# PAGE2_ATMEL.net
KiCad netlist of a schematic drawn in Altium Designer
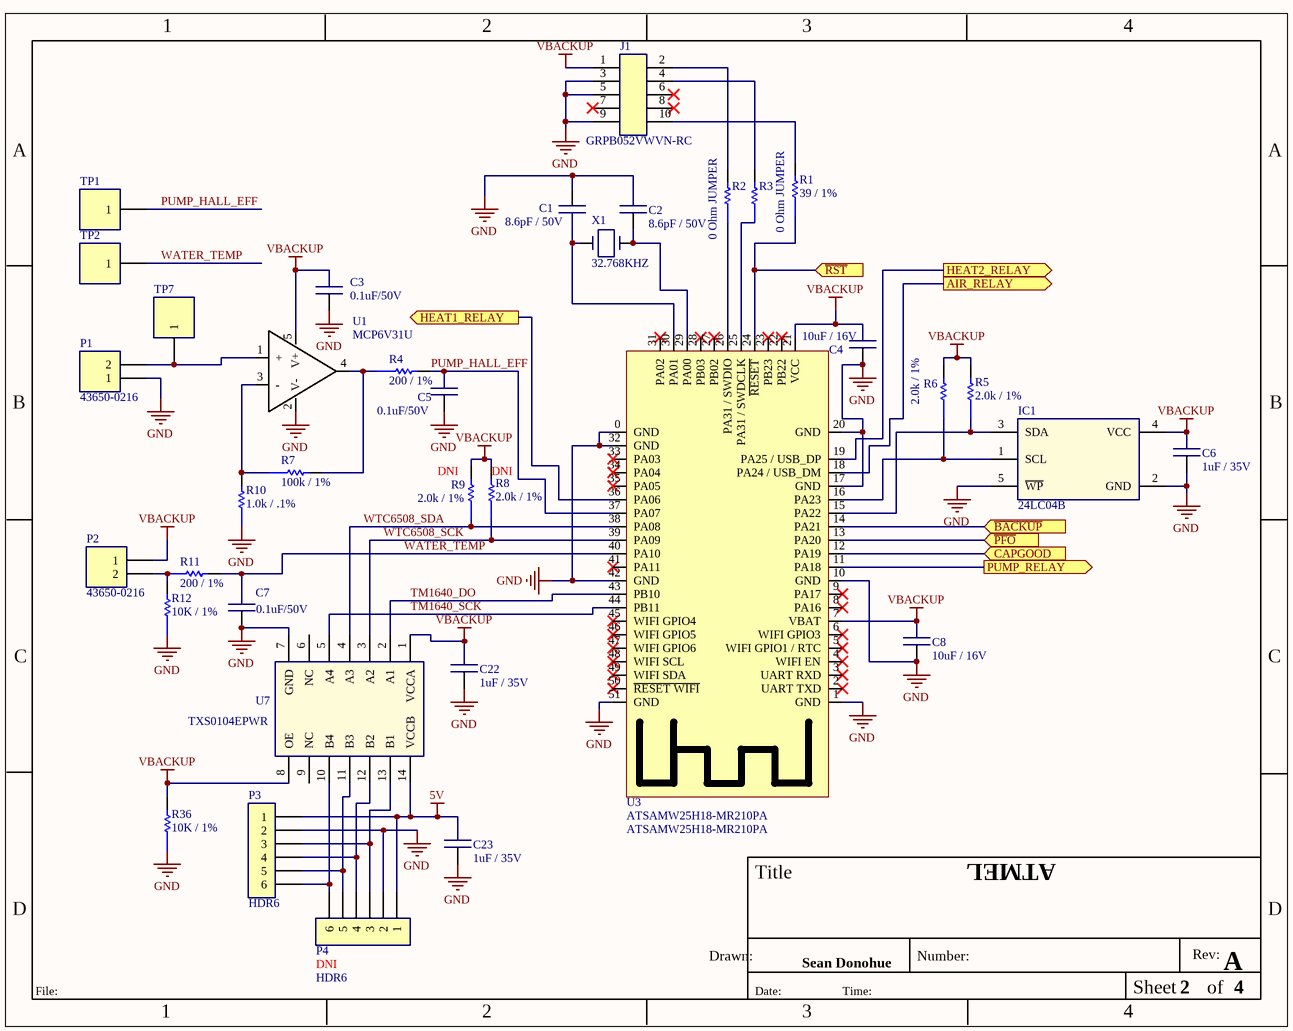
[diagram p0: PAGE2_ATMEL.SchDoc]

(export (version "E")
  (design (tool "Eeschema 10.0.6"))
  (components
    (comp (ref "C1")
      (value "8.6pF / 50V")
      (footprint "0603")
      (description "CAP CER 8.2PF 50V NP0 0603")
      (fields (field (name "MFG") "KEMET") (field (name "Comment") "cap"))
      (libsource (lib "eetrex comp db") (part "cap"))
    )
    (comp (ref "C2")
      (value "8.6pF / 50V")
      (footprint "0603")
      (description "CAP CER 8.2PF 50V NP0 0603")
      (fields (field (name "MFG") "KEMET") (field (name "Comment") "cap"))
      (libsource (lib "eetrex comp db") (part "cap"))
    )
    (comp (ref "C3")
      (value "0.1uF/50V")
      (footprint "0603")
      (description "CAP CER 0.1UF 50V 10% X7R 0603")
      (fields (field (name "MFG") "Murata") (field (name "Comment") "cap"))
      (libsource (lib "eetrex comp db") (part "cap"))
    )
    (comp (ref "C4")
      (value "10uF / 16V")
      (footprint "0603")
      (description "CAP CER 10UF 16V X5R 0603")
      (fields (field (name "MFG") "Taiyo Uden") (field (name "Comment") "cap"))
      (libsource (lib "eetrex comp db") (part "cap"))
    )
    (comp (ref "C5")
      (value "0.1uF/50V")
      (footprint "0603")
      (description "CAP CER 0.1UF 50V 10% X7R 0603")
      (fields (field (name "MFG") "Murata") (field (name "Comment") "cap"))
      (libsource (lib "eetrex comp db") (part "cap"))
    )
    (comp (ref "C6")
      (value "1uF / 35V")
      (footprint "0603")
      (description "CAP CER 1UF 35V X7R 0603")
      (fields (field (name "MFG") "Murata") (field (name "Comment") "cap"))
      (libsource (lib "eetrex comp db") (part "cap"))
    )
    (comp (ref "C7")
      (value "0.1uF/50V")
      (footprint "0603")
      (description "CAP CER 0.1UF 50V 10% X7R 0603")
      (fields (field (name "MFG") "Murata") (field (name "Comment") "cap"))
      (libsource (lib "eetrex comp db") (part "cap"))
    )
    (comp (ref "C8")
      (value "10uF / 16V")
      (footprint "0603")
      (description "CAP CER 10UF 16V X5R 0603")
      (fields (field (name "MFG") "Taiyo Uden") (field (name "Comment") "cap"))
      (libsource (lib "eetrex comp db") (part "cap"))
    )
    (comp (ref "C22")
      (value "1uF / 35V")
      (footprint "0603")
      (description "CAP CER 1UF 35V X7R 0603")
      (fields (field (name "MFG") "Murata") (field (name "Comment") "cap"))
      (libsource (lib "eetrex comp db") (part "cap"))
    )
    (comp (ref "C23")
      (value "1uF / 35V")
      (footprint "0603")
      (description "CAP CER 1UF 35V X7R 0603")
      (fields (field (name "MFG") "Murata") (field (name "Comment") "cap"))
      (libsource (lib "eetrex comp db") (part "cap"))
    )
    (comp (ref "IC1")
      (value "24LC04B")
      (footprint "SOT-23-5")
      (description "IC SERIAL EEPROM 4K 2.5V SOT23-5")
      (fields (field (name "MFG") "Microchip"))
      (libsource (lib "eetrex comp db") (part "24LC04B"))
    )
    (comp (ref "J1")
      (value "GRPB052VWVN-RC")
      (footprint "conn_10p_050mil")
      (description "CONN HEADER 10POS 1.27MM GOLD T/H")
      (fields (field (name "MFG") "Sullins") (field (name "Comment") "Header 10D"))
      (libsource (lib "eetrex comp db") (part "Header 10D"))
    )
    (comp (ref "P1")
      (value "43650-0216")
      (footprint "conn_molex_2p_43650-0215")
      (description "CONN HEADER 2POS 3MM VERT GOLD")
      (fields (field (name "MFG") "Molex") (field (name "Comment") "Header 2"))
      (libsource (lib "eetrex comp db") (part "Header 2"))
    )
    (comp (ref "P2")
      (value "43650-0216")
      (footprint "conn_molex_2p_43650-0215")
      (description "CONN HEADER 2POS 3MM VERT GOLD")
      (fields (field (name "MFG") "Molex") (field (name "Comment") "Header 2"))
      (libsource (lib "") (part "Header 2_1"))
    )
    (comp (ref "P3")
      (value "HDR6")
      (footprint "HDR1X6")
      (description "CONN HEADER 6POS .330 tall, TIN")
      (fields (field (name "MFG") "Samtec") (field (name "Comment") "Header 6"))
      (libsource (lib "eetrex comp db") (part "Header 6"))
    )
    (comp (ref "P4")
      (value "HDR6")
      (footprint "HDR1X6")
      (description "CONN HEADER 6POS .330 tall, TIN")
      (fields (field (name "MFG") "Samtec") (field (name "LOAD") "DNI") (field (name "Comment") "Header 6"))
      (libsource (lib "eetrex comp db") (part "Header 6"))
    )
    (comp (ref "R1")
      (value "39 / 1%")
      (footprint "0603")
      (description "RES 39 OHM 1% 1/10W 0603 SMD")
      (fields (field (name "MFG") "Panasonic") (field (name "Comment") "Res"))
      (libsource (lib "eetrex comp db") (part "Res"))
    )
    (comp (ref "R2")
      (value " 0 Ohm JUMPER")
      (footprint "0603")
      (description "RES 0.0 OHM 1/10W 0603 SMD")
      (fields (field (name "MFG") "Stackpole") (field (name "Comment") "Res"))
      (libsource (lib "eetrex comp db") (part "Res"))
    )
    (comp (ref "R3")
      (value " 0 Ohm JUMPER")
      (footprint "0603")
      (description "RES 0.0 OHM 1/10W 0603 SMD")
      (fields (field (name "MFG") "Stackpole") (field (name "Comment") "Res"))
      (libsource (lib "eetrex comp db") (part "Res"))
    )
    (comp (ref "R4")
      (value "200 / 1%")
      (footprint "0603")
      (description "RES 200 OHM 1% 1/10W 0603 SMD")
      (fields (field (name "MFG") "Panasonic") (field (name "Comment") "Res"))
      (libsource (lib "eetrex comp db") (part "Res"))
    )
    (comp (ref "R5")
      (value "2.0k / 1%")
      (footprint "0603")
      (description "RES 2.00K OHM 1/10W 1% 0603 SMD")
      (fields (field (name "MFG") "Vishay") (field (name "Comment") "Res"))
      (libsource (lib "eetrex comp db") (part "Res"))
    )
    (comp (ref "R6")
      (value "2.0k / 1%")
      (footprint "0603")
      (description "RES 2.00K OHM 1/10W 1% 0603 SMD")
      (fields (field (name "MFG") "Vishay") (field (name "Comment") "Res"))
      (libsource (lib "eetrex comp db") (part "Res"))
    )
    (comp (ref "R7")
      (value "100k / 1%")
      (footprint "0603")
      (description "RES 100K OHM 1/10W 1% 0603 SMD")
      (fields (field (name "MFG") "Panasonic") (field (name "Comment") "Res"))
      (libsource (lib "eetrex comp db") (part "Res"))
    )
    (comp (ref "R8")
      (value "2.0k / 1%")
      (footprint "0603")
      (description "RES 2.00K OHM 1/10W 1% 0603 SMD")
      (fields (field (name "MFG") "Vishay") (field (name "LOAD") "DNI") (field (name "Comment") "Res"))
      (libsource (lib "eetrex comp db") (part "Res"))
    )
    (comp (ref "R9")
      (value "2.0k / 1%")
      (footprint "0603")
      (description "RES 2.00K OHM 1/10W 1% 0603 SMD")
      (fields (field (name "MFG") "Vishay") (field (name "LOAD") "DNI") (field (name "Comment") "Res"))
      (libsource (lib "eetrex comp db") (part "Res"))
    )
    (comp (ref "R10")
      (value "1.0k / .1%")
      (footprint "0603")
      (description "RES 1.0K OHM 1/10W .1% 0603 SMD")
      (fields (field (name "MFG") "Panasonic") (field (name "Comment") "Res"))
      (libsource (lib "eetrex comp db") (part "Res"))
    )
    (comp (ref "R11")
      (value "200 / 1%")
      (footprint "0603")
      (description "RES 200 OHM 1% 1/10W 0603 SMD")
      (fields (field (name "MFG") "Panasonic") (field (name "Comment") "Res"))
      (libsource (lib "eetrex comp db") (part "Res"))
    )
    (comp (ref "R12")
      (value "10K / 1%")
      (footprint "0603")
      (description "RES 10K OHM 1% 1/8W 0603 SMD")
      (fields (field (name "MFG") "Vishay") (field (name "Comment") "Res"))
      (libsource (lib "eetrex comp db") (part "Res"))
    )
    (comp (ref "R36")
      (value "10K / 1%")
      (footprint "0603")
      (description "RES 10K OHM 1% 1/8W 0603 SMD")
      (fields (field (name "MFG") "Vishay") (field (name "Comment") "Res"))
      (libsource (lib "eetrex comp db") (part "Res"))
    )
    (comp (ref "TP1")
      (value "Header 1")
      (footprint "HDR1")
      (description "CONN HEADER 1POS .330 tall, TIN")
      (fields (field (name "MFG") "Samtec"))
      (libsource (lib "eetrex comp db") (part "Header 1"))
    )
    (comp (ref "TP2")
      (value "Header 1")
      (footprint "HDR1")
      (description "CONN HEADER 1POS .330 tall, TIN")
      (fields (field (name "MFG") "Samtec"))
      (libsource (lib "eetrex comp db") (part "Header 1"))
    )
    (comp (ref "TP7")
      (value "Header 1")
      (footprint "HDR1")
      (description "CONN HEADER 1POS .330 tall, TIN")
      (fields (field (name "MFG") "Samtec"))
      (libsource (lib "") (part "Header 1_1"))
    )
    (comp (ref "U1")
      (value "MCP6V31U")
      (footprint "SOT-23-5")
      (description "IC OPAMP ZRO-DRFT 300KHZ SC70-5")
      (fields (field (name "MFG") "MicroChip"))
      (libsource (lib "eetrex comp db") (part "MCP6V31U"))
    )
    (comp (ref "U3")
      (value "ATSAMW25H18-MR210PA")
      (footprint "ATSAMW25H18-MR210PA")
      (description "RF TXRX MODULE WIFI TRACE ANT")
      (fields (field (name "ALTIUM_VALUE") "ATSAMW25H18-MR210PA") (field (name "MFG") "Atmel"))
      (libsource (lib "eetrex comp db") (part "ATSAMW25H18-MR210PA"))
    )
    (comp (ref "U7")
      (value "TXS0104EPWR")
      (footprint "TSSOP-14")
      (description "IC 4BIT NON-INV TRANSLTR 14TSSOP")
      (fields (field (name "MFG") "Texas Instruments"))
      (libsource (lib "eetrex comp db") (part "TXS0104EPWR"))
    )
    (comp (ref "X1")
      (value "32.768KHZ")
      (footprint "FC-13F")
      (description "CRYSTAL 32.768KHZ 7PF SMD")
      (fields (field (name "MFG") "AVX") (field (name "Comment") "crystal"))
      (libsource (lib "eetrex comp db") (part "crystal"))
    )
  )
  (nets
    (net (code "1") (name "/AIR_RELAY") (class "Default")
      (node (ref "U3") (pin "18") (pinfunction "PA24_/_USB_DM_18") (pintype "passive"))
    )
    (net (code "2") (name "/CAPGOOD") (class "Default")
      (node (ref "U3") (pin "12") (pinfunction "PA19_12") (pintype "passive"))
    )
    (net (code "3") (name "/HEAT1_RELAY") (class "Default")
      (node (ref "U3") (pin "36") (pinfunction "PA06_36") (pintype "passive"))
    )
    (net (code "4") (name "/HEAT2_RELAY") (class "Default")
      (node (ref "U3") (pin "19") (pinfunction "PA25_/_USB_DP_19") (pintype "passive"))
    )
    (net (code "5") (name "/PUMP_HALL_EFF") (class "Default")
      (node (ref "C5") (pin "1") (pinfunction "1_1") (pintype "passive"))
      (node (ref "R4") (pin "2") (pinfunction "2_2") (pintype "passive"))
      (node (ref "TP1") (pin "1") (pinfunction "1_1") (pintype "passive"))
      (node (ref "U3") (pin "37") (pinfunction "PA07_37") (pintype "passive"))
    )
    (net (code "6") (name "/PUMP_RELAY") (class "Default")
      (node (ref "U3") (pin "11") (pinfunction "PA18_11") (pintype "passive"))
    )
    (net (code "7") (name "/TM1640_DO") (class "Default")
      (node (ref "U3") (pin "43") (pinfunction "PB10_43") (pintype "passive"))
      (node (ref "U7") (pin "2") (pinfunction "A1_2") (pintype "passive"))
    )
    (net (code "8") (name "/TM1640_SCK") (class "Default")
      (node (ref "U3") (pin "44") (pinfunction "PB11_44") (pintype "passive"))
      (node (ref "U7") (pin "5") (pinfunction "A4_5") (pintype "passive"))
    )
    (net (code "9") (name "/WATER_TEMP") (class "Default")
      (node (ref "C7") (pin "1") (pinfunction "1_1") (pintype "passive"))
      (node (ref "R11") (pin "2") (pinfunction "2_2") (pintype "passive"))
      (node (ref "TP2") (pin "1") (pinfunction "1_1") (pintype "passive"))
      (node (ref "U3") (pin "40") (pinfunction "PA10_40") (pintype "passive"))
    )
    (net (code "10") (name "/WTC6508_SCK") (class "Default")
      (node (ref "R8") (pin "1") (pinfunction "1_1") (pintype "passive"))
      (node (ref "U3") (pin "39") (pinfunction "PA09_39") (pintype "passive"))
      (node (ref "U7") (pin "3") (pinfunction "A2_3") (pintype "passive"))
    )
    (net (code "11") (name "/WTC6508_SDA") (class "Default")
      (node (ref "R9") (pin "1") (pinfunction "1_1") (pintype "passive"))
      (node (ref "U3") (pin "38") (pinfunction "PA08_38") (pintype "passive"))
      (node (ref "U7") (pin "4") (pinfunction "A3_4") (pintype "passive"))
    )
    (net (code "12") (name "/~{BACKUP}") (class "Default")
      (node (ref "U3") (pin "14") (pinfunction "PA21_14") (pintype "passive"))
    )
    (net (code "13") (name "/~{PFO}") (class "Default")
      (node (ref "U3") (pin "13") (pinfunction "PA20_13") (pintype "passive"))
    )
    (net (code "14") (name "/~{RST}") (class "Default")
      (node (ref "R1") (pin "1") (pinfunction "1_1") (pintype "passive"))
      (node (ref "U3") (pin "24") (pinfunction "~{RESET}_24") (pintype "passive"))
    )
    (net (code "15") (name "5V") (class "Default")
      (node (ref "C23") (pin "1") (pinfunction "1_1") (pintype "passive"))
      (node (ref "P3") (pin "1") (pinfunction "1_1") (pintype "passive"))
      (node (ref "P4") (pin "1") (pinfunction "1_1") (pintype "passive"))
      (node (ref "U7") (pin "14") (pinfunction "VCCB_14") (pintype "passive"))
    )
    (net (code "16") (name "GND") (class "Default")
      (node (ref "C1") (pin "2") (pinfunction "2_2") (pintype "passive"))
      (node (ref "C2") (pin "1") (pinfunction "1_1") (pintype "passive"))
      (node (ref "C22") (pin "2") (pinfunction "2_2") (pintype "passive"))
      (node (ref "C23") (pin "2") (pinfunction "2_2") (pintype "passive"))
      (node (ref "C3") (pin "2") (pinfunction "2_2") (pintype "passive"))
      (node (ref "C4") (pin "2") (pinfunction "2_2") (pintype "passive"))
      (node (ref "C5") (pin "2") (pinfunction "2_2") (pintype "passive"))
      (node (ref "C6") (pin "2") (pinfunction "2_2") (pintype "passive"))
      (node (ref "C7") (pin "2") (pinfunction "2_2") (pintype "passive"))
      (node (ref "C8") (pin "2") (pinfunction "2_2") (pintype "passive"))
      (node (ref "IC1") (pin "2") (pinfunction "GND_2") (pintype "passive"))
      (node (ref "IC1") (pin "5") (pinfunction "WP_5") (pintype "passive"))
      (node (ref "J1") (pin "3") (pinfunction "3_3") (pintype "passive"))
      (node (ref "J1") (pin "5") (pinfunction "5_5") (pintype "passive"))
      (node (ref "J1") (pin "9") (pinfunction "9_9") (pintype "passive"))
      (node (ref "P1") (pin "1") (pinfunction "1_1") (pintype "passive"))
      (node (ref "P3") (pin "2") (pinfunction "2_2") (pintype "passive"))
      (node (ref "P4") (pin "2") (pinfunction "2_2") (pintype "passive"))
      (node (ref "R10") (pin "1") (pinfunction "1_1") (pintype "passive"))
      (node (ref "R12") (pin "1") (pinfunction "1_1") (pintype "passive"))
      (node (ref "R36") (pin "1") (pinfunction "1_1") (pintype "passive"))
      (node (ref "U1") (pin "2") (pinfunction "V-_2") (pintype "passive"))
      (node (ref "U3") (pin "0") (pinfunction "GND_0") (pintype "passive"))
      (node (ref "U3") (pin "1") (pinfunction "GND_1") (pintype "passive"))
      (node (ref "U3") (pin "10") (pinfunction "GND_10") (pintype "passive"))
      (node (ref "U3") (pin "17") (pinfunction "GND_17") (pintype "passive"))
      (node (ref "U3") (pin "20") (pinfunction "GND_20") (pintype "passive"))
      (node (ref "U3") (pin "32") (pinfunction "GND_32") (pintype "passive"))
      (node (ref "U3") (pin "42") (pinfunction "GND_42") (pintype "passive"))
      (node (ref "U3") (pin "51") (pinfunction "GND_51") (pintype "passive"))
      (node (ref "U7") (pin "7") (pinfunction "GND_7") (pintype "passive"))
    )
    (net (code "17") (name "Net-(IC1-SCL)") (class "Default")
      (node (ref "IC1") (pin "1") (pinfunction "SCL_1") (pintype "passive"))
      (node (ref "R6") (pin "1") (pinfunction "1_1") (pintype "passive"))
      (node (ref "U3") (pin "16") (pinfunction "PA23_16") (pintype "passive"))
    )
    (net (code "18") (name "Net-(IC1-SDA)") (class "Default")
      (node (ref "IC1") (pin "3") (pinfunction "SDA_3") (pintype "passive"))
      (node (ref "R5") (pin "1") (pinfunction "1_1") (pintype "passive"))
      (node (ref "U3") (pin "15") (pinfunction "PA22_15") (pintype "passive"))
    )
    (net (code "19") (name "Net-(J1-Pad2)") (class "Default")
      (node (ref "J1") (pin "2") (pinfunction "2_2") (pintype "passive"))
      (node (ref "R2") (pin "2") (pinfunction "2_2") (pintype "passive"))
    )
    (net (code "20") (name "Net-(J1-Pad4)") (class "Default")
      (node (ref "J1") (pin "4") (pinfunction "4_4") (pintype "passive"))
      (node (ref "R3") (pin "2") (pinfunction "2_2") (pintype "passive"))
    )
    (net (code "21") (name "Net-(J1-Pad10)") (class "Default")
      (node (ref "J1") (pin "10") (pinfunction "10_10") (pintype "passive"))
      (node (ref "R1") (pin "2") (pinfunction "2_2") (pintype "passive"))
    )
    (net (code "22") (name "Net-(P2-Pad2)") (class "Default")
      (node (ref "P2") (pin "2") (pinfunction "2_2") (pintype "passive"))
      (node (ref "R11") (pin "1") (pinfunction "1_1") (pintype "passive"))
      (node (ref "R12") (pin "2") (pinfunction "2_2") (pintype "passive"))
    )
    (net (code "23") (name "Net-(U1-+)") (class "Default")
      (node (ref "P1") (pin "2") (pinfunction "2_2") (pintype "passive"))
      (node (ref "TP7") (pin "1") (pinfunction "1_1") (pintype "passive"))
      (node (ref "U1") (pin "1") (pinfunction "+_1") (pintype "passive"))
    )
    (net (code "24") (name "Net-(U1--)") (class "Default")
      (node (ref "R10") (pin "2") (pinfunction "2_2") (pintype "passive"))
      (node (ref "R7") (pin "1") (pinfunction "1_1") (pintype "passive"))
      (node (ref "U1") (pin "3") (pinfunction "-_3") (pintype "passive"))
    )
    (net (code "25") (name "Net-(U1-OUTA)") (class "Default")
      (node (ref "R4") (pin "1") (pinfunction "1_1") (pintype "passive"))
      (node (ref "R7") (pin "2") (pinfunction "2_2") (pintype "passive"))
      (node (ref "U1") (pin "4") (pinfunction "OUTA_4") (pintype "passive"))
    )
    (net (code "26") (name "Net-(U3-PA00)") (class "Default")
      (node (ref "C2") (pin "2") (pinfunction "2_2") (pintype "passive"))
      (node (ref "U3") (pin "29") (pinfunction "PA00_29") (pintype "passive"))
      (node (ref "X1") (pin "2") (pinfunction "2_2") (pintype "passive"))
    )
    (net (code "27") (name "Net-(U3-PA01)") (class "Default")
      (node (ref "C1") (pin "1") (pinfunction "1_1") (pintype "passive"))
      (node (ref "U3") (pin "30") (pinfunction "PA01_30") (pintype "passive"))
      (node (ref "X1") (pin "1") (pinfunction "1_1") (pintype "passive"))
    )
    (net (code "28") (name "Net-(U3-PA31_{slash}_SWDCLK)") (class "Default")
      (node (ref "R3") (pin "1") (pinfunction "1_1") (pintype "passive"))
      (node (ref "U3") (pin "25") (pinfunction "PA31_/_SWDCLK_25") (pintype "passive"))
    )
    (net (code "29") (name "Net-(U3-PA31_{slash}_SWDIO)") (class "Default")
      (node (ref "R2") (pin "1") (pinfunction "1_1") (pintype "passive"))
      (node (ref "U3") (pin "26") (pinfunction "PA31_/_SWDIO_26") (pintype "passive"))
    )
    (net (code "30") (name "Net-(U7-B1)") (class "Default")
      (node (ref "P3") (pin "3") (pinfunction "3_3") (pintype "passive"))
      (node (ref "P4") (pin "3") (pinfunction "3_3") (pintype "passive"))
      (node (ref "U7") (pin "13") (pinfunction "B1_13") (pintype "passive"))
    )
    (net (code "31") (name "Net-(U7-B2)") (class "Default")
      (node (ref "P3") (pin "4") (pinfunction "4_4") (pintype "passive"))
      (node (ref "P4") (pin "4") (pinfunction "4_4") (pintype "passive"))
      (node (ref "U7") (pin "12") (pinfunction "B2_12") (pintype "passive"))
    )
    (net (code "32") (name "Net-(U7-B3)") (class "Default")
      (node (ref "P3") (pin "5") (pinfunction "5_5") (pintype "passive"))
      (node (ref "P4") (pin "5") (pinfunction "5_5") (pintype "passive"))
      (node (ref "U7") (pin "11") (pinfunction "B3_11") (pintype "passive"))
    )
    (net (code "33") (name "Net-(U7-B4)") (class "Default")
      (node (ref "P3") (pin "6") (pinfunction "6_6") (pintype "passive"))
      (node (ref "P4") (pin "6") (pinfunction "6_6") (pintype "passive"))
      (node (ref "U7") (pin "10") (pinfunction "B4_10") (pintype "passive"))
    )
    (net (code "34") (name "VBACKUP") (class "Default")
      (node (ref "C22") (pin "1") (pinfunction "1_1") (pintype "passive"))
      (node (ref "C3") (pin "1") (pinfunction "1_1") (pintype "passive"))
      (node (ref "C4") (pin "1") (pinfunction "1_1") (pintype "passive"))
      (node (ref "C6") (pin "1") (pinfunction "1_1") (pintype "passive"))
      (node (ref "C8") (pin "1") (pinfunction "1_1") (pintype "passive"))
      (node (ref "IC1") (pin "4") (pinfunction "VCC_4") (pintype "passive"))
      (node (ref "J1") (pin "1") (pinfunction "1_1") (pintype "passive"))
      (node (ref "P2") (pin "1") (pinfunction "1_1") (pintype "passive"))
      (node (ref "R36") (pin "2") (pinfunction "2_2") (pintype "passive"))
      (node (ref "R5") (pin "2") (pinfunction "2_2") (pintype "passive"))
      (node (ref "R6") (pin "2") (pinfunction "2_2") (pintype "passive"))
      (node (ref "R8") (pin "2") (pinfunction "2_2") (pintype "passive"))
      (node (ref "R9") (pin "2") (pinfunction "2_2") (pintype "passive"))
      (node (ref "U1") (pin "5") (pinfunction "V+_5") (pintype "passive"))
      (node (ref "U3") (pin "21") (pinfunction "VCC_21") (pintype "passive"))
      (node (ref "U3") (pin "7") (pinfunction "VBAT_7") (pintype "passive"))
      (node (ref "U7") (pin "1") (pinfunction "VCCA_1") (pintype "passive"))
      (node (ref "U7") (pin "8") (pinfunction "OE_8") (pintype "passive"))
    )
    (net (code "35") (name "unconnected-(J1-Pad6)") (class "Default")
      (node (ref "J1") (pin "6") (pinfunction "6_6") (pintype "passive+no_connect"))
    )
    (net (code "36") (name "unconnected-(J1-Pad7)") (class "Default")
      (node (ref "J1") (pin "7") (pinfunction "7_7") (pintype "passive+no_connect"))
    )
    (net (code "37") (name "unconnected-(J1-Pad8)") (class "Default")
      (node (ref "J1") (pin "8") (pinfunction "8_8") (pintype "passive+no_connect"))
    )
    (net (code "38") (name "unconnected-(U3-PA02-Pad31)") (class "Default")
      (node (ref "U3") (pin "31") (pinfunction "PA02_31") (pintype "passive+no_connect"))
    )
    (net (code "39") (name "unconnected-(U3-PA03-Pad33)") (class "Default")
      (node (ref "U3") (pin "33") (pinfunction "PA03_33") (pintype "passive+no_connect"))
    )
    (net (code "40") (name "unconnected-(U3-PA04-Pad34)") (class "Default")
      (node (ref "U3") (pin "34") (pinfunction "PA04_34") (pintype "passive+no_connect"))
    )
    (net (code "41") (name "unconnected-(U3-PA05-Pad35)") (class "Default")
      (node (ref "U3") (pin "35") (pinfunction "PA05_35") (pintype "passive+no_connect"))
    )
    (net (code "42") (name "unconnected-(U3-PA11-Pad41)") (class "Default")
      (node (ref "U3") (pin "41") (pinfunction "PA11_41") (pintype "passive+no_connect"))
    )
    (net (code "43") (name "unconnected-(U3-PA16-Pad8)") (class "Default")
      (node (ref "U3") (pin "8") (pinfunction "PA16_8") (pintype "passive+no_connect"))
    )
    (net (code "44") (name "unconnected-(U3-PA17-Pad9)") (class "Default")
      (node (ref "U3") (pin "9") (pinfunction "PA17_9") (pintype "passive+no_connect"))
    )
    (net (code "45") (name "unconnected-(U3-PB02-Pad27)") (class "Default")
      (node (ref "U3") (pin "27") (pinfunction "PB02_27") (pintype "passive+no_connect"))
    )
    (net (code "46") (name "unconnected-(U3-PB03-Pad28)") (class "Default")
      (node (ref "U3") (pin "28") (pinfunction "PB03_28") (pintype "passive+no_connect"))
    )
    (net (code "47") (name "unconnected-(U3-PB22-Pad22)") (class "Default")
      (node (ref "U3") (pin "22") (pinfunction "PB22_22") (pintype "passive+no_connect"))
    )
    (net (code "48") (name "unconnected-(U3-PB23-Pad23)") (class "Default")
      (node (ref "U3") (pin "23") (pinfunction "PB23_23") (pintype "passive+no_connect"))
    )
    (net (code "49") (name "unconnected-(U3-UART_RXD-Pad3)") (class "Default")
      (node (ref "U3") (pin "3") (pinfunction "UART_RXD_3") (pintype "passive+no_connect"))
    )
    (net (code "50") (name "unconnected-(U3-UART_TXD-Pad2)") (class "Default")
      (node (ref "U3") (pin "2") (pinfunction "UART_TXD_2") (pintype "passive+no_connect"))
    )
    (net (code "51") (name "unconnected-(U3-WIFI_EN-Pad4)") (class "Default")
      (node (ref "U3") (pin "4") (pinfunction "WIFI_EN_4") (pintype "passive+no_connect"))
    )
    (net (code "52") (name "unconnected-(U3-WIFI_GPIO1_{slash}_RTC-Pad5)") (class "Default")
      (node (ref "U3") (pin "5") (pinfunction "WIFI_GPIO1_/_RTC_5") (pintype "passive+no_connect"))
    )
    (net (code "53") (name "unconnected-(U3-WIFI_GPIO3-Pad6)") (class "Default")
      (node (ref "U3") (pin "6") (pinfunction "WIFI_GPIO3_6") (pintype "passive+no_connect"))
    )
    (net (code "54") (name "unconnected-(U3-WIFI_GPIO4-Pad45)") (class "Default")
      (node (ref "U3") (pin "45") (pinfunction "WIFI_GPIO4_45") (pintype "passive+no_connect"))
    )
    (net (code "55") (name "unconnected-(U3-WIFI_GPIO5-Pad46)") (class "Default")
      (node (ref "U3") (pin "46") (pinfunction "WIFI_GPIO5_46") (pintype "passive+no_connect"))
    )
    (net (code "56") (name "unconnected-(U3-WIFI_GPIO6-Pad47)") (class "Default")
      (node (ref "U3") (pin "47") (pinfunction "WIFI_GPIO6_47") (pintype "passive+no_connect"))
    )
    (net (code "57") (name "unconnected-(U3-WIFI_SCL-Pad48)") (class "Default")
      (node (ref "U3") (pin "48") (pinfunction "WIFI_SCL_48") (pintype "passive+no_connect"))
    )
    (net (code "58") (name "unconnected-(U3-WIFI_SDA-Pad49)") (class "Default")
      (node (ref "U3") (pin "49") (pinfunction "WIFI_SDA_49") (pintype "passive+no_connect"))
    )
    (net (code "59") (name "unconnected-(U3-~{RESET_WIFI}-Pad50)") (class "Default")
      (node (ref "U3") (pin "50") (pinfunction "~{RESET_WIFI}_50") (pintype "passive+no_connect"))
    )
    (net (code "60") (name "unconnected-(U7-NC-Pad6)") (class "Default")
      (node (ref "U7") (pin "6") (pinfunction "NC_6") (pintype "passive"))
    )
    (net (code "61") (name "unconnected-(U7-NC-Pad9)") (class "Default")
      (node (ref "U7") (pin "9") (pinfunction "NC_9") (pintype "passive"))
    )
  )
)
